# Kello_uC.net
KiCad netlist of a schematic drawn in Altium Designer
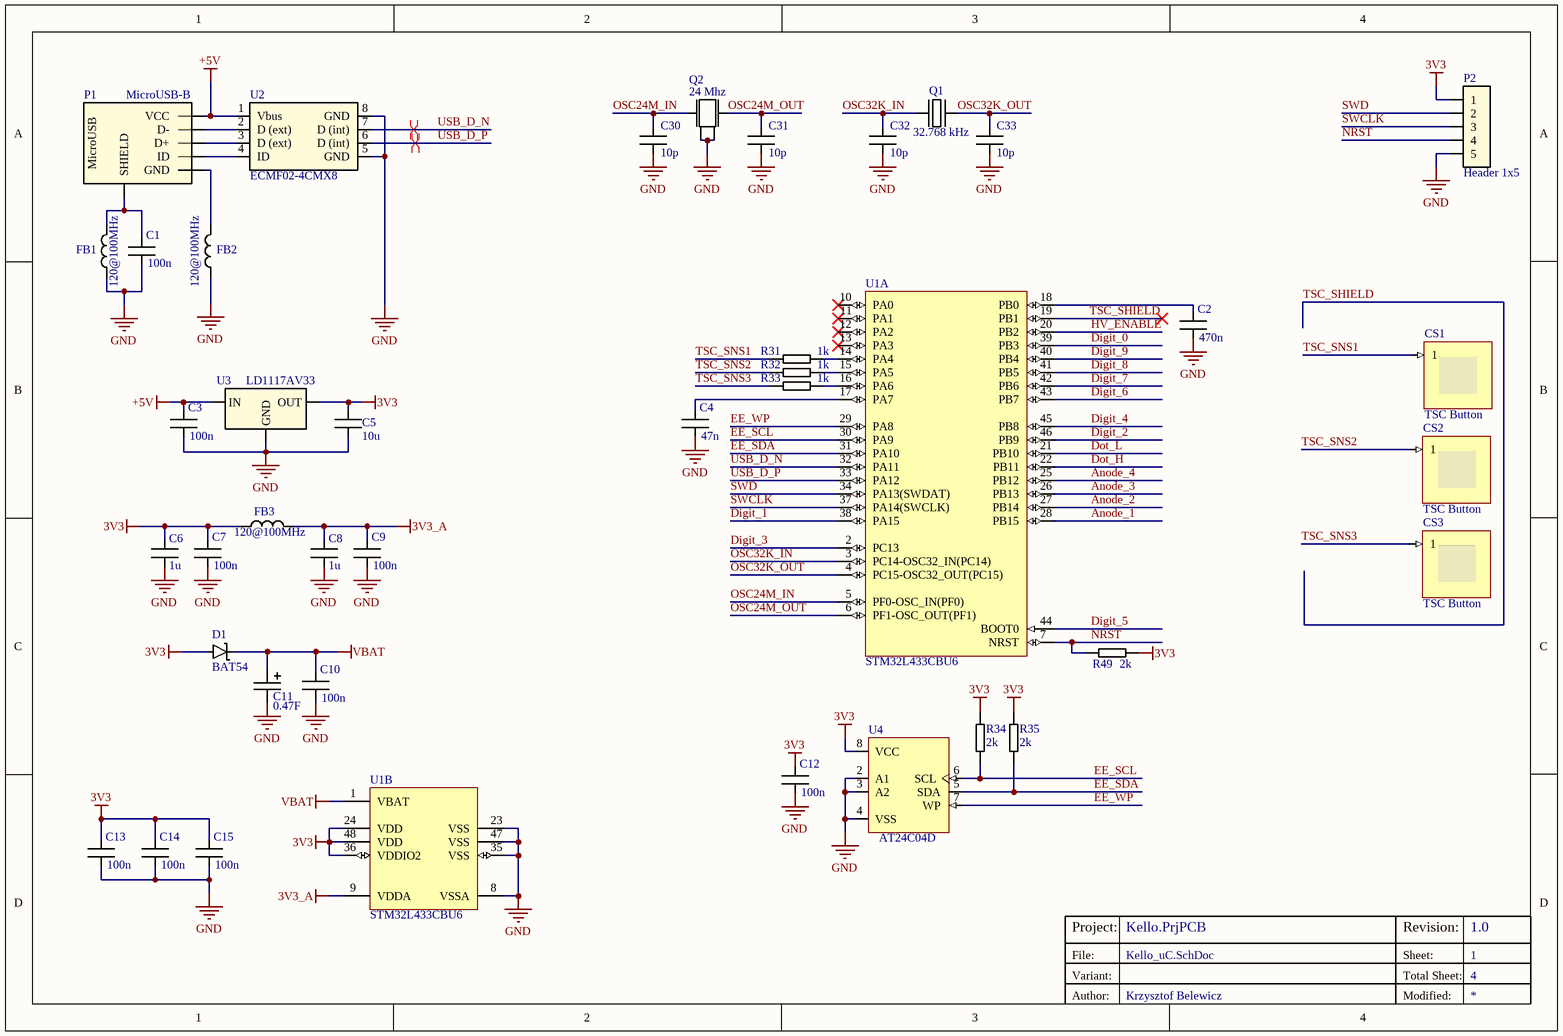
[diagram p0: Kello_uC.SchDoc]

(export (version "E")
  (design (tool "Eeschema 10.0.6"))
  (components
    (comp (ref "C1")
      (value "100n")
      (footprint "CAPC1608N")
      (description "Capacitor")
      (fields (field (name "TOLERANCE") "-20/+80%"))
      (libsource (lib "RLC") (part "Capacitor"))
    )
    (comp (ref "C2")
      (value "470n")
      (footprint "CAPC1608N")
      (description "Capacitor")
      (fields (field (name "TOLERANCE") "10%"))
      (libsource (lib "RLC") (part "Capacitor"))
    )
    (comp (ref "C3")
      (value "100n")
      (footprint "CAPC1608N")
      (description "Capacitor")
      (fields (field (name "TOLERANCE") "-20/+80%"))
      (libsource (lib "RLC") (part "Capacitor"))
    )
    (comp (ref "C4")
      (value "47n")
      (footprint "CAPC1608N")
      (description "Capacitor")
      (fields (field (name "TOLERANCE") "10%"))
      (libsource (lib "RLC") (part "Capacitor"))
    )
    (comp (ref "C5")
      (value "10u")
      (footprint "CAPC1608N")
      (description "Capacitor")
      (fields (field (name "TOLERANCE") "20%"))
      (libsource (lib "RLC") (part "Capacitor"))
    )
    (comp (ref "C6")
      (value "1u")
      (footprint "CAPC1608N")
      (description "Capacitor")
      (fields (field (name "TOLERANCE") "10%"))
      (libsource (lib "RLC") (part "Capacitor"))
    )
    (comp (ref "C7")
      (value "100n")
      (footprint "CAPC1608N")
      (description "Capacitor")
      (fields (field (name "TOLERANCE") "-20/+80%"))
      (libsource (lib "RLC") (part "Capacitor"))
    )
    (comp (ref "C8")
      (value "1u")
      (footprint "CAPC1608N")
      (description "Capacitor")
      (fields (field (name "TOLERANCE") "10%"))
      (libsource (lib "RLC") (part "Capacitor"))
    )
    (comp (ref "C9")
      (value "100n")
      (footprint "CAPC1608N")
      (description "Capacitor")
      (fields (field (name "TOLERANCE") "-20/+80%"))
      (libsource (lib "RLC") (part "Capacitor"))
    )
    (comp (ref "C10")
      (value "100n")
      (footprint "CAPC1608N")
      (description "Capacitor")
      (fields (field (name "TOLERANCE") "-20/+80%"))
      (libsource (lib "RLC") (part "Capacitor"))
    )
    (comp (ref "C11")
      (value "0.47F")
      (footprint "FGH0V474ZF")
      (description "Kondensator: elektrolityczny; 0.47F; 3,5VDC; ESR:25Ω; SMD; -20÷+80%")
      (libsource (lib "KEMET") (part "FGH0V474ZF"))
    )
    (comp (ref "C12")
      (value "100n")
      (footprint "CAPC1608N")
      (description "Capacitor")
      (fields (field (name "TOLERANCE") "-20/+80%"))
      (libsource (lib "RLC") (part "Capacitor"))
    )
    (comp (ref "C13")
      (value "100n")
      (footprint "CAPC1608N")
      (description "Capacitor")
      (fields (field (name "TOLERANCE") "-20/+80%"))
      (libsource (lib "RLC") (part "Capacitor"))
    )
    (comp (ref "C14")
      (value "100n")
      (footprint "CAPC1608N")
      (description "Capacitor")
      (fields (field (name "TOLERANCE") "-20/+80%"))
      (libsource (lib "RLC") (part "Capacitor"))
    )
    (comp (ref "C15")
      (value "100n")
      (footprint "CAPC1608N")
      (description "Capacitor")
      (fields (field (name "TOLERANCE") "-20/+80%"))
      (libsource (lib "RLC") (part "Capacitor"))
    )
    (comp (ref "C30")
      (value "10p")
      (footprint "CAPC1005N")
      (description "Capacitor")
      (fields (field (name "TOLERANCE") "1%"))
      (libsource (lib "RLC") (part "Capacitor"))
    )
    (comp (ref "C31")
      (value "10p")
      (footprint "CAPC1005N")
      (description "Capacitor")
      (fields (field (name "TOLERANCE") "1%"))
      (libsource (lib "RLC") (part "Capacitor"))
    )
    (comp (ref "C32")
      (value "10p")
      (footprint "CAPC1005N")
      (description "Capacitor")
      (fields (field (name "TOLERANCE") "1%"))
      (libsource (lib "RLC") (part "Capacitor"))
    )
    (comp (ref "C33")
      (value "10p")
      (footprint "CAPC1005N")
      (description "Capacitor")
      (fields (field (name "TOLERANCE") "1%"))
      (libsource (lib "RLC") (part "Capacitor"))
    )
    (comp (ref "CS1")
      (value "TSC Button")
      (description "QTouch Button")
      (libsource (lib "Atmel QTouch") (part "QTouchButton"))
    )
    (comp (ref "CS2")
      (value "TSC Button")
      (description "QTouch Button")
      (libsource (lib "Atmel QTouch") (part "QTouchButton"))
    )
    (comp (ref "CS3")
      (value "TSC Button")
      (description "QTouch Button")
      (libsource (lib "Atmel QTouch") (part "QTouchButton"))
    )
    (comp (ref "D1")
      (value "BAT54")
      (footprint "SOD-523F")
      (description "Fairchild BAT54XV2, Schottky, 200mA, 30V")
      (fields (field (name "MANUFACTURER") "Fairchild") (field (name "MANUFACTURER PART NUMBER") "BAT54XV2"))
      (libsource (lib "Diodes") (part "BAT54XV2"))
    )
    (comp (ref "FB1")
      (value "120@100MHz")
      (footprint "INDC1608N")
      (description "Ferrite Bead")
      (libsource (lib "RLC") (part "Inductor"))
    )
    (comp (ref "FB2")
      (value "120@100MHz")
      (footprint "INDC1608N")
      (description "Ferrite Bead")
      (libsource (lib "RLC") (part "Inductor"))
    )
    (comp (ref "FB3")
      (value "120@100MHz")
      (footprint "INDC1608N")
      (description "Ferrite Bead")
      (libsource (lib "") (part "Inductor_1"))
    )
    (comp (ref "P1")
      (value "MicroUSB-B")
      (footprint "MicroUSB-B (47346-0001)")
      (description "Molex MicroUSB-B, SMD (P/N 47346-0001)")
      (libsource (lib "Molex_HighSpeed") (part "47346-0001"))
    )
    (comp (ref "P2")
      (value "Header 1x5")
      (footprint "Header 1x5, Male, 2.54mm, Straight, THT")
      (description "Pin header, 1x5, 2.54mm")
      (libsource (lib "Header") (part "Header 1x5"))
    )
    (comp (ref "Q1")
      (value "32.768 kHz")
      (footprint "IL3X2")
      (fields (field (name "Comment") "Crystal 2 pin"))
      (libsource (lib "Crystal") (part "Crystal 2 pin"))
    )
    (comp (ref "Q2")
      (value "24 Mhz")
      (footprint "CFPX-5")
      (fields (field (name "Comment") "24Mhz"))
      (libsource (lib "Crystals") (part "Crystal 4 pin"))
    )
    (comp (ref "R31")
      (value "1k")
      (footprint "RESC1608N")
      (description "Resistor")
      (fields (field (name "TOLERANCE") "1%") (field (name "POWER") "0.1W"))
      (libsource (lib "RLC") (part "Resistor"))
    )
    (comp (ref "R32")
      (value "1k")
      (footprint "RESC1608N")
      (description "Resistor")
      (fields (field (name "TOLERANCE") "1%") (field (name "POWER") "0.1W"))
      (libsource (lib "RLC") (part "Resistor"))
    )
    (comp (ref "R33")
      (value "1k")
      (footprint "RESC1608N")
      (description "Resistor")
      (fields (field (name "TOLERANCE") "1%") (field (name "POWER") "0.1W"))
      (libsource (lib "RLC") (part "Resistor"))
    )
    (comp (ref "R34")
      (value "2k")
      (footprint "RESC1608N")
      (description "Resistor")
      (fields (field (name "TOLERANCE") "1%") (field (name "POWER") "0.1W"))
      (libsource (lib "RLC") (part "Resistor"))
    )
    (comp (ref "R35")
      (value "2k")
      (footprint "RESC1608N")
      (description "Resistor")
      (fields (field (name "TOLERANCE") "1%") (field (name "POWER") "0.1W"))
      (libsource (lib "RLC") (part "Resistor"))
    )
    (comp (ref "R49")
      (value "2k")
      (footprint "RESC1608N")
      (description "Resistor")
      (fields (field (name "TOLERANCE") "1%") (field (name "POWER") "0.1W"))
      (libsource (lib "RLC") (part "Resistor"))
    )
    (comp (ref "U1")
      (value "STM32L433CBU6")
      (footprint "STM-UFQFPN48_L")
      (description "ARM Cortex-M4 32-bit MCU, 128 KB Flash, 64 KB Internal RAM, 38 I/Os, 48-pin UFQFPN, -40 to 85 degC")
      (libsource (lib "STMicroelectronics STM32 L4") (part "STM32L433CBU6"))
    )
    (comp (ref "U2")
      (value "ECMF02-4CMX8")
      (footprint "uQFN-8")
      (description "STMicroelectronics Common Mode Filter with ESD protection, USB compatible")
      (fields (field (name "MANUFACTURER") "STMicroelectronics"))
      (libsource (lib "STMicroelectronics_Protective") (part "ECMF02-4CMX8"))
    )
    (comp (ref "U3")
      (value "LD1117AV33")
      (footprint "SOT223_N")
      (description "Stabilizator napięcia; LDO, liniowy, nieregulowany; 3,3V; 1A; SMD")
      (libsource (lib "STMicroelectronics_Power") (part "LD1117AS33TR"))
    )
    (comp (ref "U4")
      (value "AT24C04D")
      (footprint "DFN-MC8")
      (description "4Kbit, 1MHz, 1.7V-3.6V, I2C Serial EEPROM, 8-Pin DFN, Industrial Temperature, Tape and Reel")
      (libsource (lib "Microchip Memory I2C Serial EEPROM") (part "AT24C04D-MAHM-T"))
    )
  )
  (nets
    (net (code "1") (name "+5V") (class "Default")
      (node (ref "C3") (pin "2") (pinfunction "2_2") (pintype "passive"))
      (node (ref "P1") (pin "1") (pinfunction "VCC_1") (pintype "passive"))
      (node (ref "U2") (pin "1") (pinfunction "Vbus_1") (pintype "passive"))
      (node (ref "U3") (pin "3") (pinfunction "IN_3") (pintype "passive"))
    )
    (net (code "2") (name "/Anode_1") (class "Default")
      (node (ref "U1") (pin "28") (pinfunction "PB15_28") (pintype "bidirectional"))
    )
    (net (code "3") (name "/Anode_2") (class "Default")
      (node (ref "U1") (pin "27") (pinfunction "PB14_27") (pintype "bidirectional"))
    )
    (net (code "4") (name "/Anode_3") (class "Default")
      (node (ref "U1") (pin "26") (pinfunction "PB13_26") (pintype "bidirectional"))
    )
    (net (code "5") (name "/Anode_4") (class "Default")
      (node (ref "U1") (pin "25") (pinfunction "PB12_25") (pintype "bidirectional"))
    )
    (net (code "6") (name "/Digit_0") (class "Default")
      (node (ref "U1") (pin "39") (pinfunction "PB3_39") (pintype "bidirectional"))
    )
    (net (code "7") (name "/Digit_1") (class "Default")
      (node (ref "U1") (pin "38") (pinfunction "PA15_38") (pintype "bidirectional"))
    )
    (net (code "8") (name "/Digit_2") (class "Default")
      (node (ref "U1") (pin "46") (pinfunction "PB9_46") (pintype "bidirectional"))
    )
    (net (code "9") (name "/Digit_3") (class "Default")
      (node (ref "U1") (pin "2") (pinfunction "PC13_2") (pintype "bidirectional"))
    )
    (net (code "10") (name "/Digit_4") (class "Default")
      (node (ref "U1") (pin "45") (pinfunction "PB8_45") (pintype "bidirectional"))
    )
    (net (code "11") (name "/Digit_5") (class "Default")
      (node (ref "U1") (pin "44") (pinfunction "BOOT0_44") (pintype "input"))
    )
    (net (code "12") (name "/Digit_6") (class "Default")
      (node (ref "U1") (pin "43") (pinfunction "PB7_43") (pintype "bidirectional"))
    )
    (net (code "13") (name "/Digit_7") (class "Default")
      (node (ref "U1") (pin "42") (pinfunction "PB6_42") (pintype "bidirectional"))
    )
    (net (code "14") (name "/Digit_8") (class "Default")
      (node (ref "U1") (pin "41") (pinfunction "PB5_41") (pintype "bidirectional"))
    )
    (net (code "15") (name "/Digit_9") (class "Default")
      (node (ref "U1") (pin "40") (pinfunction "PB4_40") (pintype "bidirectional"))
    )
    (net (code "16") (name "/Dot_H") (class "Default")
      (node (ref "U1") (pin "22") (pinfunction "PB11_22") (pintype "bidirectional"))
    )
    (net (code "17") (name "/Dot_L") (class "Default")
      (node (ref "U1") (pin "21") (pinfunction "PB10_21") (pintype "bidirectional"))
    )
    (net (code "18") (name "/EE_SCL") (class "Default")
      (node (ref "R34") (pin "2") (pinfunction "2_2") (pintype "passive"))
      (node (ref "U1") (pin "30") (pinfunction "PA9_30") (pintype "bidirectional"))
      (node (ref "U4") (pin "6") (pinfunction "SCL_6") (pintype "input"))
    )
    (net (code "19") (name "/EE_SDA") (class "Default")
      (node (ref "R35") (pin "2") (pinfunction "2_2") (pintype "passive"))
      (node (ref "U1") (pin "31") (pinfunction "PA10_31") (pintype "bidirectional"))
      (node (ref "U4") (pin "5") (pinfunction "SDA_5") (pintype "bidirectional"))
    )
    (net (code "20") (name "/EE_WP") (class "Default")
      (node (ref "U1") (pin "29") (pinfunction "PA8_29") (pintype "bidirectional"))
      (node (ref "U4") (pin "7") (pinfunction "WP_7") (pintype "input"))
    )
    (net (code "21") (name "/HV_ENABLE") (class "Default")
      (node (ref "U1") (pin "20") (pinfunction "PB2_20") (pintype "bidirectional"))
    )
    (net (code "22") (name "/NRST") (class "Default")
      (node (ref "P2") (pin "4") (pinfunction "4_4") (pintype "passive"))
      (node (ref "R49") (pin "1") (pinfunction "1_1") (pintype "passive"))
      (node (ref "U1") (pin "7") (pinfunction "NRST_7") (pintype "bidirectional"))
    )
    (net (code "23") (name "/OSC24M_IN") (class "Default")
      (node (ref "C30") (pin "2") (pinfunction "2_2") (pintype "passive"))
      (node (ref "Q2") (pin "1") (pinfunction "1_1") (pintype "passive"))
      (node (ref "U1") (pin "5") (pinfunction "PF0-OSC_IN(PF0)_5") (pintype "bidirectional"))
    )
    (net (code "24") (name "/OSC24M_OUT") (class "Default")
      (node (ref "C31") (pin "2") (pinfunction "2_2") (pintype "passive"))
      (node (ref "Q2") (pin "3") (pinfunction "3_3") (pintype "passive"))
      (node (ref "U1") (pin "6") (pinfunction "PF1-OSC_OUT(PF1)_6") (pintype "bidirectional"))
    )
    (net (code "25") (name "/OSC32K_IN") (class "Default")
      (node (ref "C32") (pin "2") (pinfunction "2_2") (pintype "passive"))
      (node (ref "Q1") (pin "1") (pinfunction "1_1") (pintype "passive"))
      (node (ref "U1") (pin "3") (pinfunction "PC14-OSC32_IN(PC14)_3") (pintype "bidirectional"))
    )
    (net (code "26") (name "/OSC32K_OUT") (class "Default")
      (node (ref "C33") (pin "2") (pinfunction "2_2") (pintype "passive"))
      (node (ref "Q1") (pin "2") (pinfunction "2_2") (pintype "passive"))
      (node (ref "U1") (pin "4") (pinfunction "PC15-OSC32_OUT(PC15)_4") (pintype "bidirectional"))
    )
    (net (code "27") (name "/SWCLK") (class "Default")
      (node (ref "P2") (pin "3") (pinfunction "3_3") (pintype "passive"))
      (node (ref "U1") (pin "37") (pinfunction "PA14(SWCLK)_37") (pintype "bidirectional"))
    )
    (net (code "28") (name "/SWD") (class "Default")
      (node (ref "P2") (pin "2") (pinfunction "2_2") (pintype "passive"))
      (node (ref "U1") (pin "34") (pinfunction "PA13(SWDAT)_34") (pintype "bidirectional"))
    )
    (net (code "29") (name "/TSC_SHIELD") (class "Default")
      (node (ref "U1") (pin "19") (pinfunction "PB1_19") (pintype "bidirectional+no_connect"))
    )
    (net (code "30") (name "/TSC_SNS1") (class "Default")
      (node (ref "CS1") (pin "1") (pinfunction "1_1") (pintype "input"))
      (node (ref "R31") (pin "1") (pinfunction "1_1") (pintype "passive"))
    )
    (net (code "31") (name "/TSC_SNS2") (class "Default")
      (node (ref "CS2") (pin "1") (pinfunction "1_1") (pintype "input"))
      (node (ref "R32") (pin "1") (pinfunction "1_1") (pintype "passive"))
    )
    (net (code "32") (name "/TSC_SNS3") (class "Default")
      (node (ref "CS3") (pin "1") (pinfunction "1_1") (pintype "input"))
      (node (ref "R33") (pin "1") (pinfunction "1_1") (pintype "passive"))
    )
    (net (code "33") (name "/USB_D_N") (class "Default")
      (node (ref "U1") (pin "32") (pinfunction "PA11_32") (pintype "bidirectional"))
      (node (ref "U2") (pin "7") (pinfunction "D_(int)_7") (pintype "passive"))
    )
    (net (code "34") (name "/USB_D_P") (class "Default")
      (node (ref "U1") (pin "33") (pinfunction "PA12_33") (pintype "bidirectional"))
      (node (ref "U2") (pin "6") (pinfunction "D_(int)_6") (pintype "passive"))
    )
    (net (code "35") (name "3V3") (class "Default")
      (node (ref "C12") (pin "2") (pinfunction "2_2") (pintype "passive"))
      (node (ref "C13") (pin "2") (pinfunction "2_2") (pintype "passive"))
      (node (ref "C14") (pin "2") (pinfunction "2_2") (pintype "passive"))
      (node (ref "C15") (pin "2") (pinfunction "2_2") (pintype "passive"))
      (node (ref "C5") (pin "2") (pinfunction "2_2") (pintype "passive"))
      (node (ref "C6") (pin "2") (pinfunction "2_2") (pintype "passive"))
      (node (ref "C7") (pin "2") (pinfunction "2_2") (pintype "passive"))
      (node (ref "D1") (pin "A") (pinfunction "A_A") (pintype "passive"))
      (node (ref "FB3") (pin "1") (pinfunction "1_1") (pintype "passive"))
      (node (ref "P2") (pin "1") (pinfunction "1_1") (pintype "passive"))
      (node (ref "R34") (pin "1") (pinfunction "1_1") (pintype "passive"))
      (node (ref "R35") (pin "1") (pinfunction "1_1") (pintype "passive"))
      (node (ref "R49") (pin "2") (pinfunction "2_2") (pintype "passive"))
      (node (ref "U1") (pin "24") (pinfunction "VDD_24") (pintype "power_in"))
      (node (ref "U1") (pin "36") (pinfunction "VDDIO2_36") (pintype "bidirectional"))
      (node (ref "U1") (pin "48") (pinfunction "VDD_48") (pintype "power_in"))
      (node (ref "U3") (pin "2") (pinfunction "OUT_2") (pintype "passive"))
      (node (ref "U4") (pin "8") (pinfunction "VCC_8") (pintype "power_in"))
    )
    (net (code "36") (name "3V3_A") (class "Default")
      (node (ref "C8") (pin "2") (pinfunction "2_2") (pintype "passive"))
      (node (ref "C9") (pin "2") (pinfunction "2_2") (pintype "passive"))
      (node (ref "FB3") (pin "2") (pinfunction "2_2") (pintype "passive"))
      (node (ref "U1") (pin "9") (pinfunction "VDDA_9") (pintype "power_in"))
    )
    (net (code "37") (name "GND") (class "Default")
      (node (ref "C1") (pin "1") (pinfunction "1_1") (pintype "passive"))
      (node (ref "C10") (pin "1") (pinfunction "1_1") (pintype "passive"))
      (node (ref "C11") (pin "2") (pinfunction "2_2") (pintype "passive"))
      (node (ref "C12") (pin "1") (pinfunction "1_1") (pintype "passive"))
      (node (ref "C13") (pin "1") (pinfunction "1_1") (pintype "passive"))
      (node (ref "C14") (pin "1") (pinfunction "1_1") (pintype "passive"))
      (node (ref "C15") (pin "1") (pinfunction "1_1") (pintype "passive"))
      (node (ref "C2") (pin "1") (pinfunction "1_1") (pintype "passive"))
      (node (ref "C3") (pin "1") (pinfunction "1_1") (pintype "passive"))
      (node (ref "C30") (pin "1") (pinfunction "1_1") (pintype "passive"))
      (node (ref "C31") (pin "1") (pinfunction "1_1") (pintype "passive"))
      (node (ref "C32") (pin "1") (pinfunction "1_1") (pintype "passive"))
      (node (ref "C33") (pin "1") (pinfunction "1_1") (pintype "passive"))
      (node (ref "C4") (pin "1") (pinfunction "1_1") (pintype "passive"))
      (node (ref "C5") (pin "1") (pinfunction "1_1") (pintype "passive"))
      (node (ref "C6") (pin "1") (pinfunction "1_1") (pintype "passive"))
      (node (ref "C7") (pin "1") (pinfunction "1_1") (pintype "passive"))
      (node (ref "C8") (pin "1") (pinfunction "1_1") (pintype "passive"))
      (node (ref "C9") (pin "1") (pinfunction "1_1") (pintype "passive"))
      (node (ref "FB1") (pin "2") (pinfunction "2_2") (pintype "passive"))
      (node (ref "FB2") (pin "2") (pinfunction "2_2") (pintype "passive"))
      (node (ref "P2") (pin "5") (pinfunction "5_5") (pintype "passive"))
      (node (ref "Q2") (pin "2") (pinfunction "2_2") (pintype "passive"))
      (node (ref "Q2") (pin "4") (pinfunction "4_4") (pintype "passive"))
      (node (ref "U1") (pin "23") (pinfunction "VSS_23") (pintype "power_in"))
      (node (ref "U1") (pin "35") (pinfunction "VSS_35") (pintype "bidirectional"))
      (node (ref "U1") (pin "47") (pinfunction "VSS_47") (pintype "power_in"))
      (node (ref "U1") (pin "8") (pinfunction "VSSA_8") (pintype "power_in"))
      (node (ref "U2") (pin "5") (pinfunction "GND_5") (pintype "passive"))
      (node (ref "U2") (pin "8") (pinfunction "GND_8") (pintype "passive"))
      (node (ref "U3") (pin "1") (pinfunction "GND_1") (pintype "passive"))
      (node (ref "U4") (pin "2") (pinfunction "A1_2") (pintype "passive"))
      (node (ref "U4") (pin "3") (pinfunction "A2_3") (pintype "passive"))
      (node (ref "U4") (pin "4") (pinfunction "VSS_4") (pintype "power_in"))
    )
    (net (code "38") (name "Net-(P1-D+)") (class "Default")
      (node (ref "P1") (pin "3") (pinfunction "D+_3") (pintype "passive"))
      (node (ref "U2") (pin "3") (pinfunction "D_(ext)_3") (pintype "passive"))
    )
    (net (code "39") (name "Net-(P1-D-)") (class "Default")
      (node (ref "P1") (pin "2") (pinfunction "D-_2") (pintype "passive"))
      (node (ref "U2") (pin "2") (pinfunction "D_(ext)_2") (pintype "passive"))
    )
    (net (code "40") (name "Net-(P1-GND)") (class "Default")
      (node (ref "FB2") (pin "1") (pinfunction "1_1") (pintype "passive"))
      (node (ref "P1") (pin "5") (pinfunction "GND_5") (pintype "passive"))
    )
    (net (code "41") (name "Net-(P1-ID)") (class "Default")
      (node (ref "P1") (pin "4") (pinfunction "ID_4") (pintype "passive"))
      (node (ref "U2") (pin "4") (pinfunction "ID_4") (pintype "passive"))
    )
    (net (code "42") (name "Net-(P1-SHIELD)") (class "Default")
      (node (ref "C1") (pin "2") (pinfunction "2_2") (pintype "passive"))
      (node (ref "FB1") (pin "1") (pinfunction "1_1") (pintype "passive"))
      (node (ref "P1") (pin "6") (pinfunction "SHIELD_6") (pintype "passive"))
    )
    (net (code "43") (name "Net-(U1A-PA4)") (class "Default")
      (node (ref "R31") (pin "2") (pinfunction "2_2") (pintype "passive"))
      (node (ref "U1") (pin "14") (pinfunction "PA4_14") (pintype "bidirectional"))
    )
    (net (code "44") (name "Net-(U1A-PA5)") (class "Default")
      (node (ref "R32") (pin "2") (pinfunction "2_2") (pintype "passive"))
      (node (ref "U1") (pin "15") (pinfunction "PA5_15") (pintype "bidirectional"))
    )
    (net (code "45") (name "Net-(U1A-PA6)") (class "Default")
      (node (ref "R33") (pin "2") (pinfunction "2_2") (pintype "passive"))
      (node (ref "U1") (pin "16") (pinfunction "PA6_16") (pintype "bidirectional"))
    )
    (net (code "46") (name "Net-(U1A-PA7)") (class "Default")
      (node (ref "C4") (pin "2") (pinfunction "2_2") (pintype "passive"))
      (node (ref "U1") (pin "17") (pinfunction "PA7_17") (pintype "bidirectional"))
    )
    (net (code "47") (name "Net-(U1A-PB0)") (class "Default")
      (node (ref "C2") (pin "2") (pinfunction "2_2") (pintype "passive"))
      (node (ref "U1") (pin "18") (pinfunction "PB0_18") (pintype "bidirectional"))
    )
    (net (code "48") (name "VBAT") (class "Default")
      (node (ref "C10") (pin "2") (pinfunction "2_2") (pintype "passive"))
      (node (ref "C11") (pin "1") (pinfunction "1_1") (pintype "passive"))
      (node (ref "D1") (pin "K") (pinfunction "K_K") (pintype "passive"))
      (node (ref "U1") (pin "1") (pinfunction "VBAT_1") (pintype "power_in"))
    )
    (net (code "49") (name "unconnected-(U1A-PA0-Pad10)") (class "Default")
      (node (ref "U1") (pin "10") (pinfunction "PA0_10") (pintype "bidirectional+no_connect"))
    )
    (net (code "50") (name "unconnected-(U1A-PA1-Pad11)") (class "Default")
      (node (ref "U1") (pin "11") (pinfunction "PA1_11") (pintype "bidirectional+no_connect"))
    )
    (net (code "51") (name "unconnected-(U1A-PA2-Pad12)") (class "Default")
      (node (ref "U1") (pin "12") (pinfunction "PA2_12") (pintype "bidirectional+no_connect"))
    )
    (net (code "52") (name "unconnected-(U1A-PA3-Pad13)") (class "Default")
      (node (ref "U1") (pin "13") (pinfunction "PA3_13") (pintype "bidirectional+no_connect"))
    )
  )
)
